# power.net
KiCad netlist of a schematic drawn in Altium Designer
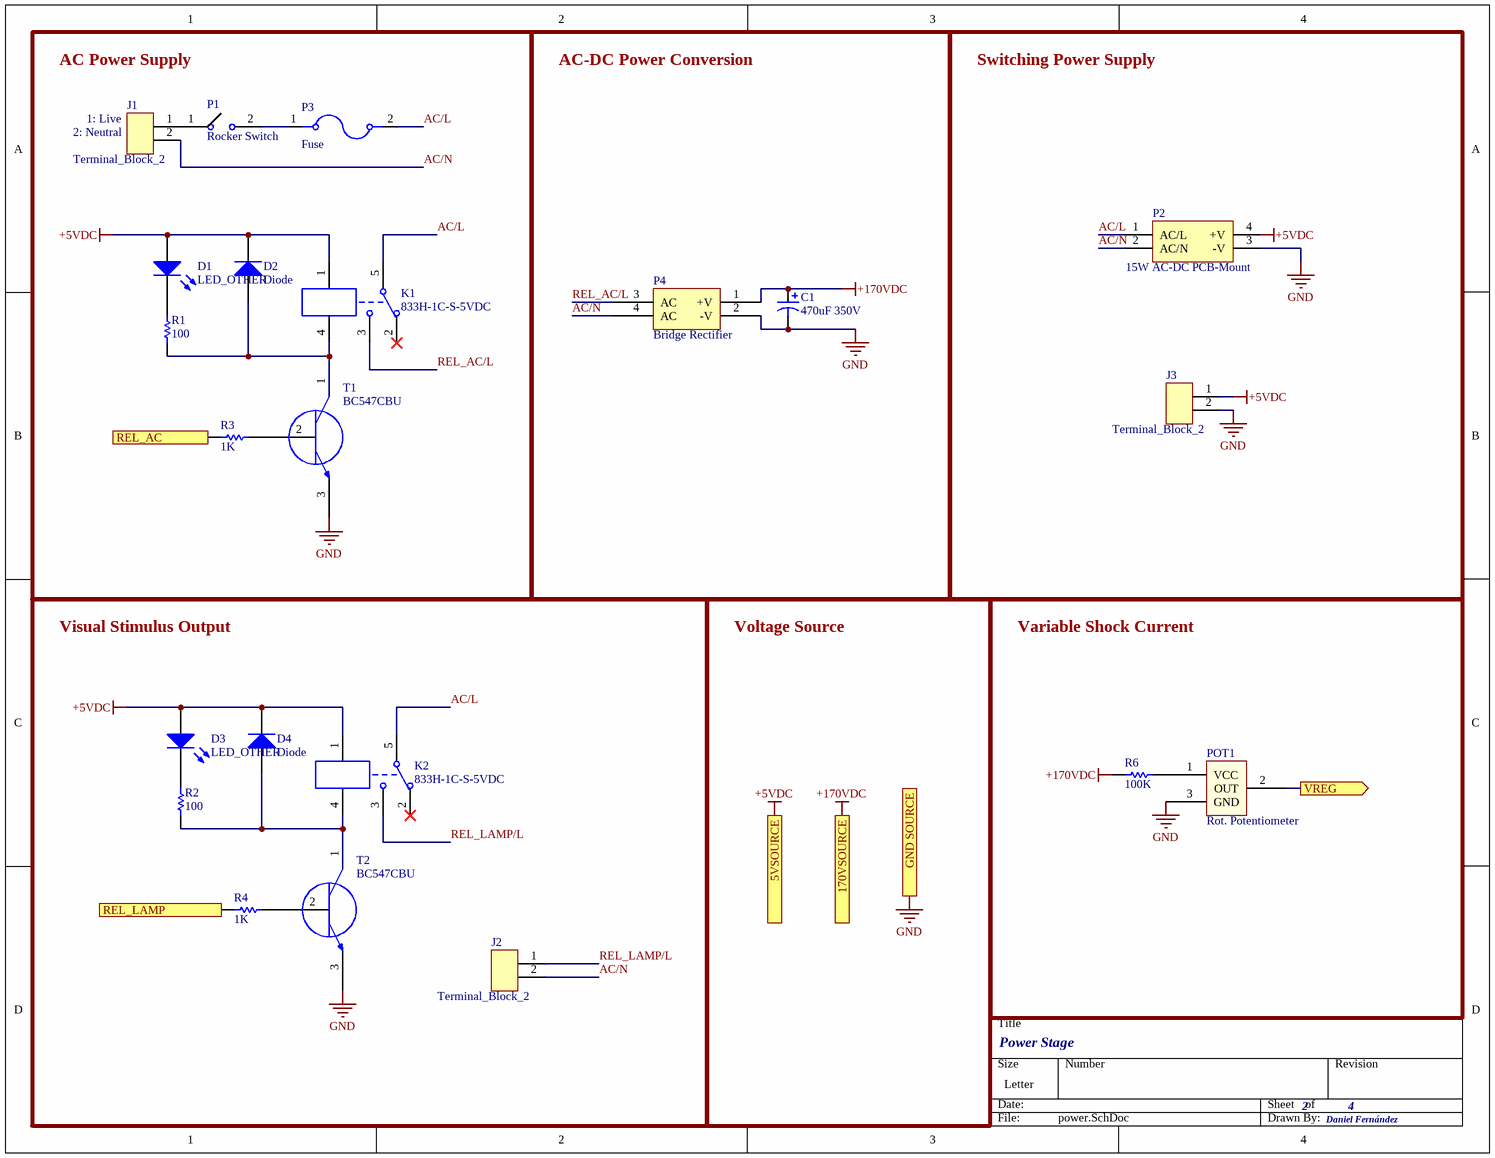
[diagram p0: power.SchDoc]

(export (version "E")
  (design (tool "Eeschema 10.0.6"))
  (components
    (comp (ref "C1")
      (value "470uF 350V")
      (footprint "ESMQ351VSN471MR35S")
      (description "Capacitor_AXIAL_Pol")
      (libsource (lib "PERCRO_schematic") (part "Capacitor_AXIAL_Pol"))
    )
    (comp (ref "D1")
      (value "LED_OTHER")
      (footprint "PERCRO_footprints:LED_AXIAL")
      (description "Typical RED GaAs LED")
      (fields (field (name "PUBLISHER") "Altium Limited"))
      (libsource (lib "PERCRO_schematic") (part "LED_OTHER"))
    )
    (comp (ref "D2")
      (value "Diode")
      (footprint "Diodo 1N4007 Rectificador")
      (description "Default Diode")
      (fields (field (name "PUBLISHER") "Altium Limited"))
      (libsource (lib "PERCRO_schematic") (part "Diode"))
    )
    (comp (ref "D3")
      (value "LED_OTHER")
      (footprint "PERCRO_footprints:LED_AXIAL")
      (description "Typical RED GaAs LED")
      (fields (field (name "PUBLISHER") "Altium Limited"))
      (libsource (lib "PERCRO_schematic") (part "LED_OTHER"))
    )
    (comp (ref "D4")
      (value "Diode")
      (footprint "Diodo 1N4007 Rectificador")
      (description "Default Diode")
      (fields (field (name "PUBLISHER") "Altium Limited"))
      (libsource (lib "PERCRO_schematic") (part "Diode"))
    )
    (comp (ref "J1")
      (value "Terminal_Block_2")
      (footprint "Terminal_Block_2")
      (libsource (lib "Components_Schematics") (part "Terminal_Block_2"))
    )
    (comp (ref "J2")
      (value "Terminal_Block_2")
      (footprint "Terminal_Block_2")
      (libsource (lib "Components_Schematics") (part "Terminal_Block_2"))
    )
    (comp (ref "J3")
      (value "Terminal_Block_2")
      (footprint "Terminal_Block_2")
      (libsource (lib "Components_Schematics") (part "Terminal_Block_2"))
    )
    (comp (ref "K1")
      (value "833H-1C-S-5VDC")
      (footprint "PERCRO_footprints:Relay_833H")
      (description "Relay Song Chuan 5V")
      (fields (field (name "MANUFACTURER") "Song Chuan"))
      (libsource (lib "PERCRO_schematic") (part "Relay_Song 5V"))
    )
    (comp (ref "K2")
      (value "833H-1C-S-5VDC")
      (footprint "PERCRO_footprints:Relay_833H")
      (description "Relay Song Chuan 5V")
      (fields (field (name "MANUFACTURER") "Song Chuan"))
      (libsource (lib "PERCRO_schematic") (part "Relay_Song 5V"))
    )
    (comp (ref "P1")
      (value "Rocker Switch")
      (footprint "Rocker Switch")
      (libsource (lib "Components_Schematics") (part "Rocker Switch"))
    )
    (comp (ref "P2")
      (value "15W AC-DC PCB-Mount")
      (footprint "15W AC-DC PCB-Mount")
      (libsource (lib "Components_Schematics") (part "15W AC-DC PCB-Mount"))
    )
    (comp (ref "P3")
      (value "Fuse")
      (footprint "Fuse Holder")
      (libsource (lib "Components_Schematics") (part "Fuse"))
    )
    (comp (ref "P4")
      (value "Bridge Rectifier")
      (footprint "KBPC1010")
      (description "Single-Phase Silicon Bridge Rectifier Rectifier")
      (libsource (lib "Components_Schematics") (part "KBPC1010"))
    )
    (comp (ref "POT1")
      (value "Rot. Potentiometer")
      (footprint "PTV09A-4020F-B504")
      (description "Rotatory Potentiometer")
      (libsource (lib "Components_Schematics") (part "ROT_POT"))
    )
    (comp (ref "R1")
      (value "100")
      (footprint "RESISTOR")
      (description "Resistor_Axial")
      (fields (field (name "PUBLISHER") "Altium Limited"))
      (libsource (lib "PERCRO_schematic") (part "Resistor_Axial"))
    )
    (comp (ref "R2")
      (value "100")
      (footprint "RESISTOR")
      (description "Resistor_Axial")
      (fields (field (name "PUBLISHER") "Altium Limited"))
      (libsource (lib "PERCRO_schematic") (part "Resistor_Axial"))
    )
    (comp (ref "R3")
      (value "1K")
      (footprint "RESISTOR")
      (description "Resistor_Axial")
      (fields (field (name "PUBLISHER") "Altium Limited"))
      (libsource (lib "PERCRO_schematic") (part "Resistor_Axial"))
    )
    (comp (ref "R4")
      (value "1K")
      (footprint "RESISTOR")
      (description "Resistor_Axial")
      (fields (field (name "PUBLISHER") "Altium Limited"))
      (libsource (lib "PERCRO_schematic") (part "Resistor_Axial"))
    )
    (comp (ref "R6")
      (value "100K")
      (footprint "RESISTOR")
      (description "Resistor_Axial")
      (fields (field (name "PUBLISHER") "Altium Limited"))
      (libsource (lib "PERCRO_schematic") (part "Resistor_Axial"))
    )
    (comp (ref "T1")
      (value "BC547CBU")
      (footprint "BC547CBU")
      (libsource (lib "Components_Schematics") (part "BC547CBU"))
    )
    (comp (ref "T2")
      (value "BC547CBU")
      (footprint "BC547CBU")
      (libsource (lib "Components_Schematics") (part "BC547CBU"))
    )
  )
  (nets
    (net (code "1") (name "+5VDC") (class "Default")
      (node (ref "D1") (pin "1") (pinfunction "A_1") (pintype "passive"))
      (node (ref "D2") (pin "2") (pinfunction "C_2") (pintype "passive"))
      (node (ref "D3") (pin "1") (pinfunction "A_1") (pintype "passive"))
      (node (ref "D4") (pin "2") (pinfunction "C_2") (pintype "passive"))
      (node (ref "J3") (pin "1") (pinfunction "1_1") (pintype "passive"))
      (node (ref "K1") (pin "1") (pinfunction "1_1") (pintype "passive"))
      (node (ref "K2") (pin "1") (pinfunction "1_1") (pintype "passive"))
      (node (ref "P2") (pin "4") (pinfunction "+V_4") (pintype "passive"))
    )
    (net (code "2") (name "+170VDC") (class "Default")
      (node (ref "C1") (pin "1") (pinfunction "1_1") (pintype "passive"))
      (node (ref "P4") (pin "1") (pinfunction "+V_1") (pintype "passive"))
      (node (ref "R6") (pin "1") (pinfunction "1_1") (pintype "passive"))
    )
    (net (code "3") (name "/AC{slash}L") (class "Default")
      (node (ref "K1") (pin "5") (pinfunction "5_5") (pintype "passive"))
      (node (ref "K2") (pin "5") (pinfunction "5_5") (pintype "passive"))
      (node (ref "P2") (pin "1") (pinfunction "AC/L_1") (pintype "passive"))
      (node (ref "P3") (pin "2") (pinfunction "2_2") (pintype "passive"))
    )
    (net (code "4") (name "/AC{slash}N") (class "Default")
      (node (ref "J1") (pin "2") (pinfunction "2_2") (pintype "passive"))
      (node (ref "J2") (pin "2") (pinfunction "2_2") (pintype "passive"))
      (node (ref "P2") (pin "2") (pinfunction "AC/N_2") (pintype "passive"))
      (node (ref "P4") (pin "4") (pinfunction "AC_4") (pintype "passive"))
    )
    (net (code "5") (name "/REL_AC") (class "Default")
      (node (ref "R3") (pin "1") (pinfunction "1_1") (pintype "passive"))
    )
    (net (code "6") (name "/REL_AC{slash}L") (class "Default")
      (node (ref "K1") (pin "3") (pinfunction "NO_3") (pintype "passive"))
      (node (ref "P4") (pin "3") (pinfunction "AC_3") (pintype "passive"))
    )
    (net (code "7") (name "/REL_LAMP") (class "Default")
      (node (ref "R4") (pin "1") (pinfunction "1_1") (pintype "passive"))
    )
    (net (code "8") (name "/REL_LAMP{slash}L") (class "Default")
      (node (ref "J2") (pin "1") (pinfunction "1_1") (pintype "passive"))
      (node (ref "K2") (pin "3") (pinfunction "NO_3") (pintype "passive"))
    )
    (net (code "9") (name "/VREG") (class "Default")
      (node (ref "POT1") (pin "2") (pinfunction "OUT_2") (pintype "passive"))
    )
    (net (code "10") (name "GND") (class "Default")
      (node (ref "C1") (pin "2") (pinfunction "2_2") (pintype "passive"))
      (node (ref "J3") (pin "2") (pinfunction "2_2") (pintype "passive"))
      (node (ref "P2") (pin "3") (pinfunction "-V_3") (pintype "passive"))
      (node (ref "P4") (pin "2") (pinfunction "-V_2") (pintype "passive"))
      (node (ref "POT1") (pin "3") (pinfunction "GND_3") (pintype "passive"))
      (node (ref "T1") (pin "3") (pinfunction "E_3") (pintype "passive"))
      (node (ref "T2") (pin "3") (pinfunction "E_3") (pintype "passive"))
    )
    (net (code "11") (name "Net-(D1-K)") (class "Default")
      (node (ref "D1") (pin "2") (pinfunction "K_2") (pintype "passive"))
      (node (ref "R1") (pin "2") (pinfunction "2_2") (pintype "passive"))
    )
    (net (code "12") (name "Net-(D2-A)") (class "Default")
      (node (ref "D2") (pin "1") (pinfunction "A_1") (pintype "passive"))
      (node (ref "K1") (pin "4") (pinfunction "4_4") (pintype "passive"))
      (node (ref "R1") (pin "1") (pinfunction "1_1") (pintype "passive"))
      (node (ref "T1") (pin "1") (pinfunction "C_1") (pintype "passive"))
    )
    (net (code "13") (name "Net-(D3-K)") (class "Default")
      (node (ref "D3") (pin "2") (pinfunction "K_2") (pintype "passive"))
      (node (ref "R2") (pin "2") (pinfunction "2_2") (pintype "passive"))
    )
    (net (code "14") (name "Net-(D4-A)") (class "Default")
      (node (ref "D4") (pin "1") (pinfunction "A_1") (pintype "passive"))
      (node (ref "K2") (pin "4") (pinfunction "4_4") (pintype "passive"))
      (node (ref "R2") (pin "1") (pinfunction "1_1") (pintype "passive"))
      (node (ref "T2") (pin "1") (pinfunction "C_1") (pintype "passive"))
    )
    (net (code "15") (name "Net-(J1-Pad1)") (class "Default")
      (node (ref "J1") (pin "1") (pinfunction "1_1") (pintype "passive"))
      (node (ref "P1") (pin "1") (pinfunction "1_1") (pintype "passive"))
    )
    (net (code "16") (name "Net-(P1-Pad2)") (class "Default")
      (node (ref "P1") (pin "2") (pinfunction "2_2") (pintype "passive"))
      (node (ref "P3") (pin "1") (pinfunction "1_1") (pintype "passive"))
    )
    (net (code "17") (name "Net-(POT1-VCC)") (class "Default")
      (node (ref "POT1") (pin "1") (pinfunction "VCC_1") (pintype "passive"))
      (node (ref "R6") (pin "2") (pinfunction "2_2") (pintype "passive"))
    )
    (net (code "18") (name "Net-(T1-B)") (class "Default")
      (node (ref "R3") (pin "2") (pinfunction "2_2") (pintype "passive"))
      (node (ref "T1") (pin "2") (pinfunction "B_2") (pintype "passive"))
    )
    (net (code "19") (name "Net-(T2-B)") (class "Default")
      (node (ref "R4") (pin "2") (pinfunction "2_2") (pintype "passive"))
      (node (ref "T2") (pin "2") (pinfunction "B_2") (pintype "passive"))
    )
    (net (code "20") (name "unconnected-(K1-NC-Pad2)") (class "Default")
      (node (ref "K1") (pin "2") (pinfunction "NC_2") (pintype "passive+no_connect"))
    )
    (net (code "21") (name "unconnected-(K2-NC-Pad2)") (class "Default")
      (node (ref "K2") (pin "2") (pinfunction "NC_2") (pintype "passive+no_connect"))
    )
  )
)
